# 08_SLAVE_CARD_CONNECTOR_RJ45.net
KiCad netlist of a schematic drawn in Altium Designer
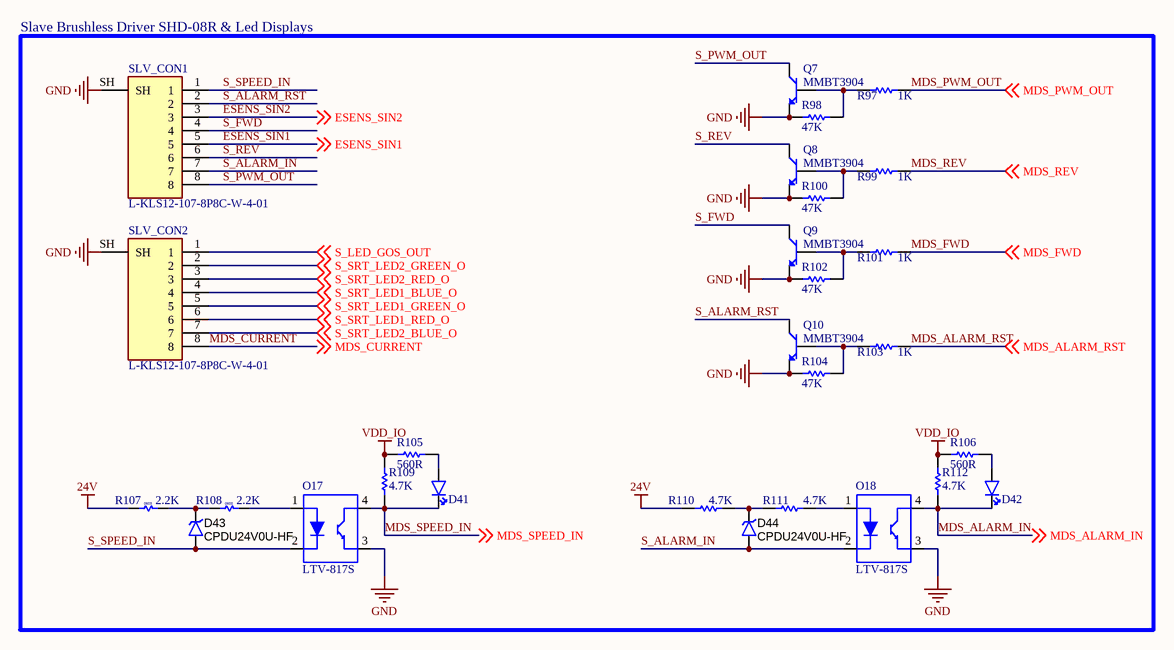
[diagram p0: 08_SLAVE_CARD_CONNECTOR_RJ45.SchDoc]

(export (version "E")
  (design (tool "Eeschema 10.0.6"))
  (components
    (comp (ref "D41")
      (value "led_green")
      (footprint "805LED")
      (description "LED 2X1.2MM 570NM GN WTR CLR SMD")
      (fields (field (name "DIGI-KEY PART NUMBER") "754-1127-1-ND"))
      (libsource (lib "FKDZ_Altium_Lib") (part "LED_GREEN_0805"))
    )
    (comp (ref "D42")
      (value "led_green")
      (footprint "805LED")
      (description "LED 2X1.2MM 570NM GN WTR CLR SMD")
      (fields (field (name "DIGI-KEY PART NUMBER") "754-1127-1-ND"))
      (libsource (lib "FKDZ_Altium_Lib") (part "LED_GREEN_0805"))
    )
    (comp (ref "D43")
      (value "CPDU24V0U-HF")
      (footprint "SOD523F")
      (description "50V Clamp 3A (8/20µs) Ipp Tvs Diode Surface Mount 0603/SOD-523F")
      (fields
        (field (name "DIGI-KEY PART NUMBER") "641-1679-1-ND")
        (field (name "MANUFACTURER") "Comchip Technology")
      )
      (libsource (lib "FKDZ_Altium_Lib") (part "TVS DIODE 24VWM 50V 0603/SOD523F CPDU24V0U-HF"))
    )
    (comp (ref "D44")
      (value "CPDU24V0U-HF")
      (footprint "SOD523F")
      (description "50V Clamp 3A (8/20µs) Ipp Tvs Diode Surface Mount 0603/SOD-523F")
      (fields
        (field (name "DIGI-KEY PART NUMBER") "641-1679-1-ND")
        (field (name "MANUFACTURER") "Comchip Technology")
      )
      (libsource (lib "FKDZ_Altium_Lib") (part "TVS DIODE 24VWM 50V 0603/SOD523F CPDU24V0U-HF"))
    )
    (comp (ref "O17")
      (value "LTV-817S")
      (footprint "SMD4-2.54-4.6X6.5MM")
      (description "Optoisolator Transistor Output 5000Vrms 1 Channel 4-SMD")
      (fields (field (name "DIGI-KEY PART NUMBER") "160-1367-5-ND"))
      (libsource (lib "FKDZ_Altium_Lib") (part "OPTOISOLATR 5KV TRANSISTOR 4-SMD LTV-817S"))
    )
    (comp (ref "O18")
      (value "LTV-817S")
      (footprint "SMD4-2.54-4.6X6.5MM")
      (description "Optoisolator Transistor Output 5000Vrms 1 Channel 4-SMD")
      (fields (field (name "DIGI-KEY PART NUMBER") "160-1367-5-ND"))
      (libsource (lib "FKDZ_Altium_Lib") (part "OPTOISOLATR 5KV TRANSISTOR 4-SMD LTV-817S"))
    )
    (comp (ref "Q7")
      (value "MMBT3904")
      (footprint "ONSC-SOT-23-3-318-08_V")
      (description "Bipolar (BJT) Transistor NPN 40V 200mA 300MHz 300mW Surface Mount SOT-23-3 (TO-236)")
      (fields
        (field (name "DIGI-KEY PART NUMBER") "MMBT3904LT3GOSTR-ND")
        (field (name "MANUFACTURER") "ON Semiconductor")
      )
      (libsource (lib "FKDZ_Altium_Lib") (part "NPN_BT3904"))
    )
    (comp (ref "Q8")
      (value "MMBT3904")
      (footprint "ONSC-SOT-23-3-318-08_V")
      (description "Bipolar (BJT) Transistor NPN 40V 200mA 300MHz 300mW Surface Mount SOT-23-3 (TO-236)")
      (fields
        (field (name "DIGI-KEY PART NUMBER") "MMBT3904LT3GOSTR-ND")
        (field (name "MANUFACTURER") "ON Semiconductor")
      )
      (libsource (lib "FKDZ_Altium_Lib") (part "NPN_BT3904"))
    )
    (comp (ref "Q9")
      (value "MMBT3904")
      (footprint "ONSC-SOT-23-3-318-08_V")
      (description "Bipolar (BJT) Transistor NPN 40V 200mA 300MHz 300mW Surface Mount SOT-23-3 (TO-236)")
      (fields
        (field (name "DIGI-KEY PART NUMBER") "MMBT3904LT3GOSTR-ND")
        (field (name "MANUFACTURER") "ON Semiconductor")
      )
      (libsource (lib "FKDZ_Altium_Lib") (part "NPN_BT3904"))
    )
    (comp (ref "Q10")
      (value "MMBT3904")
      (footprint "ONSC-SOT-23-3-318-08_V")
      (description "Bipolar (BJT) Transistor NPN 40V 200mA 300MHz 300mW Surface Mount SOT-23-3 (TO-236)")
      (fields
        (field (name "DIGI-KEY PART NUMBER") "MMBT3904LT3GOSTR-ND")
        (field (name "MANUFACTURER") "ON Semiconductor")
      )
      (libsource (lib "FKDZ_Altium_Lib") (part "NPN_BT3904"))
    )
    (comp (ref "R97")
      (value "1K")
      (footprint "603R")
      (description "1 kOhms ±5% 0.1W, 1/10W Chip Resistor 0603 (1608 Metric) Moisture Resistant Thick Film")
      (fields (field (name "DIGI-KEY PART NUMBER") "311-1.0KGRTR-ND") (field (name "MANUFACTURER") "Yageo"))
      (libsource (lib "FKDZ_Altium_Lib") (part "RES_1K_OHM_%5_0.1W_0603"))
    )
    (comp (ref "R98")
      (value "47K")
      (footprint "603R")
      (description "47 kOhms ±5% 0.1W, 1/10W Chip Resistor 0603 (1608 Metric) Moisture Resistant Thick Film")
      (fields (field (name "DIGI-KEY PART NUMBER") "311-47KGRTR-ND") (field (name "MANUFACTURER") "Yageo"))
      (libsource (lib "FKDZ_Altium_Lib") (part "RES_47K_OHM_%5_0.1W_0603"))
    )
    (comp (ref "R99")
      (value "1K")
      (footprint "603R")
      (description "1 kOhms ±5% 0.1W, 1/10W Chip Resistor 0603 (1608 Metric) Moisture Resistant Thick Film")
      (fields (field (name "DIGI-KEY PART NUMBER") "311-1.0KGRTR-ND") (field (name "MANUFACTURER") "Yageo"))
      (libsource (lib "FKDZ_Altium_Lib") (part "RES_1K_OHM_%5_0.1W_0603"))
    )
    (comp (ref "R100")
      (value "47K")
      (footprint "603R")
      (description "47 kOhms ±5% 0.1W, 1/10W Chip Resistor 0603 (1608 Metric) Moisture Resistant Thick Film")
      (fields (field (name "DIGI-KEY PART NUMBER") "311-47KGRTR-ND") (field (name "MANUFACTURER") "Yageo"))
      (libsource (lib "FKDZ_Altium_Lib") (part "RES_47K_OHM_%5_0.1W_0603"))
    )
    (comp (ref "R101")
      (value "1K")
      (footprint "603R")
      (description "1 kOhms ±5% 0.1W, 1/10W Chip Resistor 0603 (1608 Metric) Moisture Resistant Thick Film")
      (fields (field (name "DIGI-KEY PART NUMBER") "311-1.0KGRTR-ND") (field (name "MANUFACTURER") "Yageo"))
      (libsource (lib "FKDZ_Altium_Lib") (part "RES_1K_OHM_%5_0.1W_0603"))
    )
    (comp (ref "R102")
      (value "47K")
      (footprint "603R")
      (description "47 kOhms ±5% 0.1W, 1/10W Chip Resistor 0603 (1608 Metric) Moisture Resistant Thick Film")
      (fields (field (name "DIGI-KEY PART NUMBER") "311-47KGRTR-ND") (field (name "MANUFACTURER") "Yageo"))
      (libsource (lib "FKDZ_Altium_Lib") (part "RES_47K_OHM_%5_0.1W_0603"))
    )
    (comp (ref "R103")
      (value "1K")
      (footprint "603R")
      (description "1 kOhms ±5% 0.1W, 1/10W Chip Resistor 0603 (1608 Metric) Moisture Resistant Thick Film")
      (fields (field (name "DIGI-KEY PART NUMBER") "311-1.0KGRTR-ND") (field (name "MANUFACTURER") "Yageo"))
      (libsource (lib "FKDZ_Altium_Lib") (part "RES_1K_OHM_%5_0.1W_0603"))
    )
    (comp (ref "R104")
      (value "47K")
      (footprint "603R")
      (description "47 kOhms ±5% 0.1W, 1/10W Chip Resistor 0603 (1608 Metric) Moisture Resistant Thick Film")
      (fields (field (name "DIGI-KEY PART NUMBER") "311-47KGRTR-ND") (field (name "MANUFACTURER") "Yageo"))
      (libsource (lib "FKDZ_Altium_Lib") (part "RES_47K_OHM_%5_0.1W_0603"))
    )
    (comp (ref "R105")
      (value "560R")
      (footprint "603R")
      (description "560 Ohms ±5% 0.1W, 1/10W Chip Resistor 0603 (1608 Metric) Moisture Resistant Thick Film")
      (fields (field (name "DIGI-KEY PART NUMBER") "311-560GRCT-ND") (field (name "MANUFACTURER") "Yageo"))
      (libsource (lib "FKDZ_Altium_Lib") (part "RES_560_OHM_%5_0.1W_0603"))
    )
    (comp (ref "R106")
      (value "560R")
      (footprint "603R")
      (description "560 Ohms ±5% 0.1W, 1/10W Chip Resistor 0603 (1608 Metric) Moisture Resistant Thick Film")
      (fields (field (name "DIGI-KEY PART NUMBER") "311-560GRCT-ND") (field (name "MANUFACTURER") "Yageo"))
      (libsource (lib "FKDZ_Altium_Lib") (part "RES_560_OHM_%5_0.1W_0603"))
    )
    (comp (ref "R107")
      (value "2.2K")
      (footprint "603R")
      (description "2.2 kOhms ±5% 0.1W, 1/10W Chip Resistor 0603 (1608 Metric) Automotive AEC-Q200 Thick Film")
      (fields (field (name "DIGI-KEY PART NUMBER") "RMCF0603JT2K20TR-ND") (field (name "TOLERANCE") "±5%"))
      (libsource (lib "FKDZ_Altium_Lib") (part "RES 2.2K OHM 5% 1/10W 0603"))
    )
    (comp (ref "R108")
      (value "2.2K")
      (footprint "603R")
      (description "2.2 kOhms ±5% 0.1W, 1/10W Chip Resistor 0603 (1608 Metric) Automotive AEC-Q200 Thick Film")
      (fields (field (name "DIGI-KEY PART NUMBER") "RMCF0603JT2K20TR-ND") (field (name "TOLERANCE") "±5%"))
      (libsource (lib "FKDZ_Altium_Lib") (part "RES 2.2K OHM 5% 1/10W 0603"))
    )
    (comp (ref "R109")
      (value "4.7K")
      (footprint "603R")
      (description "4.7 kOhms ±5% 0.1W, 1/10W Chip Resistor 0603 (1608 Metric) Moisture Resistant Thick Film")
      (fields (field (name "DIGI-KEY PART NUMBER") "311-4.7KGRTR-ND") (field (name "MANUFACTURER") "Yageo"))
      (libsource (lib "FKDZ_Altium_Lib") (part "RES_4.7K_OHM_%5_0.1W_0603"))
    )
    (comp (ref "R110")
      (value "4.7K")
      (footprint "603R")
      (description "4.7 kOhms ±5% 0.1W, 1/10W Chip Resistor 0603 (1608 Metric) Moisture Resistant Thick Film")
      (fields (field (name "DIGI-KEY PART NUMBER") "311-4.7KGRTR-ND") (field (name "MANUFACTURER") "Yageo"))
      (libsource (lib "FKDZ_Altium_Lib") (part "RES_4.7K_OHM_%5_0.1W_0603"))
    )
    (comp (ref "R111")
      (value "4.7K")
      (footprint "603R")
      (description "4.7 kOhms ±5% 0.1W, 1/10W Chip Resistor 0603 (1608 Metric) Moisture Resistant Thick Film")
      (fields (field (name "DIGI-KEY PART NUMBER") "311-4.7KGRTR-ND") (field (name "MANUFACTURER") "Yageo"))
      (libsource (lib "FKDZ_Altium_Lib") (part "RES_4.7K_OHM_%5_0.1W_0603"))
    )
    (comp (ref "R112")
      (value "4.7K")
      (footprint "603R")
      (description "4.7 kOhms ±5% 0.1W, 1/10W Chip Resistor 0603 (1608 Metric) Moisture Resistant Thick Film")
      (fields (field (name "DIGI-KEY PART NUMBER") "311-4.7KGRTR-ND") (field (name "MANUFACTURER") "Yageo"))
      (libsource (lib "FKDZ_Altium_Lib") (part "RES_4.7K_OHM_%5_0.1W_0603"))
    )
    (comp (ref "SLV_CON1")
      (value "L-KLS12-107-8P8C-W-4-01")
      (footprint "RJ45_JACK_H L-KLS12-107-8P8C-W-4-01")
      (description "Jack Modular Connector 8p8c (RJ45, Ethernet) 90° Angle (Right) Shielded")
      (libsource (lib "FKDZ_Altium_Lib") (part "MODULAR JACK THT R/A 8P8C (RJ45,Ethernet) BLACK L-KLS12-107-8P8C-W-4-01"))
    )
    (comp (ref "SLV_CON2")
      (value "L-KLS12-107-8P8C-W-4-01")
      (footprint "RJ45_JACK_H L-KLS12-107-8P8C-W-4-01")
      (description "Jack Modular Connector 8p8c (RJ45, Ethernet) 90° Angle (Right) Shielded")
      (libsource (lib "FKDZ_Altium_Lib") (part "MODULAR JACK THT R/A 8P8C (RJ45,Ethernet) BLACK L-KLS12-107-8P8C-W-4-01"))
    )
  )
  (nets
    (net (code "1") (name "/S_ALARM_IN") (class "Default")
      (node (ref "D44") (pin "1") (pinfunction "1_1") (pintype "passive"))
      (node (ref "O18") (pin "2") (pinfunction "CATHODE_2") (pintype "passive"))
      (node (ref "SLV_CON1") (pin "7") (pinfunction "7_7") (pintype "passive"))
    )
    (net (code "2") (name "/S_ALARM_RST") (class "Default")
      (node (ref "Q10") (pin "3") (pinfunction "C_3") (pintype "passive"))
      (node (ref "SLV_CON1") (pin "2") (pinfunction "2_2") (pintype "passive"))
    )
    (net (code "3") (name "/S_FWD") (class "Default")
      (node (ref "Q9") (pin "3") (pinfunction "C_3") (pintype "passive"))
      (node (ref "SLV_CON1") (pin "4") (pinfunction "4_4") (pintype "passive"))
    )
    (net (code "4") (name "/S_PWM_OUT") (class "Default")
      (node (ref "Q7") (pin "3") (pinfunction "C_3") (pintype "passive"))
      (node (ref "SLV_CON1") (pin "8") (pinfunction "8_8") (pintype "passive"))
    )
    (net (code "5") (name "/S_REV") (class "Default")
      (node (ref "Q8") (pin "3") (pinfunction "C_3") (pintype "passive"))
      (node (ref "SLV_CON1") (pin "6") (pinfunction "6_6") (pintype "passive"))
    )
    (net (code "6") (name "/S_SPEED_IN") (class "Default")
      (node (ref "D43") (pin "1") (pinfunction "1_1") (pintype "passive"))
      (node (ref "O17") (pin "2") (pinfunction "CATHODE_2") (pintype "passive"))
      (node (ref "SLV_CON1") (pin "1") (pinfunction "1_1") (pintype "passive"))
    )
    (net (code "7") (name "24V") (class "Default")
      (node (ref "R107") (pin "1") (pinfunction "1_1") (pintype "passive"))
      (node (ref "R110") (pin "1") (pinfunction "1_1") (pintype "passive"))
    )
    (net (code "8") (name "ESENS_SIN1") (class "Default")
      (node (ref "SLV_CON1") (pin "5") (pinfunction "5_5") (pintype "passive"))
    )
    (net (code "9") (name "ESENS_SIN2") (class "Default")
      (node (ref "SLV_CON1") (pin "3") (pinfunction "3_3") (pintype "passive"))
    )
    (net (code "10") (name "GND") (class "Default")
      (node (ref "O17") (pin "3") (pinfunction "EMITER_3") (pintype "passive"))
      (node (ref "O18") (pin "3") (pinfunction "EMITER_3") (pintype "passive"))
      (node (ref "Q10") (pin "2") (pinfunction "E_2") (pintype "passive"))
      (node (ref "Q7") (pin "2") (pinfunction "E_2") (pintype "passive"))
      (node (ref "Q8") (pin "2") (pinfunction "E_2") (pintype "passive"))
      (node (ref "Q9") (pin "2") (pinfunction "E_2") (pintype "passive"))
      (node (ref "R100") (pin "1") (pinfunction "1_1") (pintype "passive"))
      (node (ref "R102") (pin "1") (pinfunction "1_1") (pintype "passive"))
      (node (ref "R104") (pin "1") (pinfunction "1_1") (pintype "passive"))
      (node (ref "R98") (pin "1") (pinfunction "1_1") (pintype "passive"))
      (node (ref "SLV_CON1") (pin "SH") (pinfunction "SH_SH") (pintype "passive"))
      (node (ref "SLV_CON2") (pin "SH") (pinfunction "SH_SH") (pintype "passive"))
    )
    (net (code "11") (name "MDS_ALARM_IN") (class "Default")
      (node (ref "D42") (pin "2") (pinfunction "K_2") (pintype "passive"))
      (node (ref "O18") (pin "4") (pinfunction "COLLECTOR_4") (pintype "passive"))
      (node (ref "R112") (pin "1") (pinfunction "1_1") (pintype "passive"))
    )
    (net (code "12") (name "MDS_ALARM_RST") (class "Default")
      (node (ref "R103") (pin "2") (pinfunction "2_2") (pintype "passive"))
    )
    (net (code "13") (name "MDS_CURRENT") (class "Default")
      (node (ref "SLV_CON2") (pin "8") (pinfunction "8_8") (pintype "passive"))
    )
    (net (code "14") (name "MDS_FWD") (class "Default")
      (node (ref "R101") (pin "2") (pinfunction "2_2") (pintype "passive"))
    )
    (net (code "15") (name "MDS_PWM_OUT") (class "Default")
      (node (ref "R97") (pin "2") (pinfunction "2_2") (pintype "passive"))
    )
    (net (code "16") (name "MDS_REV") (class "Default")
      (node (ref "R99") (pin "2") (pinfunction "2_2") (pintype "passive"))
    )
    (net (code "17") (name "MDS_SPEED_IN") (class "Default")
      (node (ref "D41") (pin "2") (pinfunction "K_2") (pintype "passive"))
      (node (ref "O17") (pin "4") (pinfunction "COLLECTOR_4") (pintype "passive"))
      (node (ref "R109") (pin "1") (pinfunction "1_1") (pintype "passive"))
    )
    (net (code "18") (name "Net-(D41-A)") (class "Default")
      (node (ref "D41") (pin "1") (pinfunction "A_1") (pintype "passive"))
      (node (ref "R105") (pin "1") (pinfunction "1_1") (pintype "passive"))
    )
    (net (code "19") (name "Net-(D42-A)") (class "Default")
      (node (ref "D42") (pin "1") (pinfunction "A_1") (pintype "passive"))
      (node (ref "R106") (pin "1") (pinfunction "1_1") (pintype "passive"))
    )
    (net (code "20") (name "Net-(D43-Pad2)") (class "Default")
      (node (ref "D43") (pin "2") (pinfunction "2_2") (pintype "passive"))
      (node (ref "R107") (pin "2") (pinfunction "2_2") (pintype "passive"))
      (node (ref "R108") (pin "1") (pinfunction "1_1") (pintype "passive"))
    )
    (net (code "21") (name "Net-(D44-Pad2)") (class "Default")
      (node (ref "D44") (pin "2") (pinfunction "2_2") (pintype "passive"))
      (node (ref "R110") (pin "2") (pinfunction "2_2") (pintype "passive"))
      (node (ref "R111") (pin "1") (pinfunction "1_1") (pintype "passive"))
    )
    (net (code "22") (name "Net-(O17-ANODE)") (class "Default")
      (node (ref "O17") (pin "1") (pinfunction "ANODE_1") (pintype "passive"))
      (node (ref "R108") (pin "2") (pinfunction "2_2") (pintype "passive"))
    )
    (net (code "23") (name "Net-(O18-ANODE)") (class "Default")
      (node (ref "O18") (pin "1") (pinfunction "ANODE_1") (pintype "passive"))
      (node (ref "R111") (pin "2") (pinfunction "2_2") (pintype "passive"))
    )
    (net (code "24") (name "Net-(Q7-B)") (class "Default")
      (node (ref "Q7") (pin "1") (pinfunction "B_1") (pintype "passive"))
      (node (ref "R97") (pin "1") (pinfunction "1_1") (pintype "passive"))
      (node (ref "R98") (pin "2") (pinfunction "2_2") (pintype "passive"))
    )
    (net (code "25") (name "Net-(Q8-B)") (class "Default")
      (node (ref "Q8") (pin "1") (pinfunction "B_1") (pintype "passive"))
      (node (ref "R100") (pin "2") (pinfunction "2_2") (pintype "passive"))
      (node (ref "R99") (pin "1") (pinfunction "1_1") (pintype "passive"))
    )
    (net (code "26") (name "Net-(Q9-B)") (class "Default")
      (node (ref "Q9") (pin "1") (pinfunction "B_1") (pintype "passive"))
      (node (ref "R101") (pin "1") (pinfunction "1_1") (pintype "passive"))
      (node (ref "R102") (pin "2") (pinfunction "2_2") (pintype "passive"))
    )
    (net (code "27") (name "Net-(Q10-B)") (class "Default")
      (node (ref "Q10") (pin "1") (pinfunction "B_1") (pintype "passive"))
      (node (ref "R103") (pin "1") (pinfunction "1_1") (pintype "passive"))
      (node (ref "R104") (pin "2") (pinfunction "2_2") (pintype "passive"))
    )
    (net (code "28") (name "S_LED_GOS_OUT") (class "Default")
      (node (ref "SLV_CON2") (pin "1") (pinfunction "1_1") (pintype "passive"))
    )
    (net (code "29") (name "S_SRT_LED1_BLUE_O") (class "Default")
      (node (ref "SLV_CON2") (pin "4") (pinfunction "4_4") (pintype "passive"))
    )
    (net (code "30") (name "S_SRT_LED1_GREEN_O") (class "Default")
      (node (ref "SLV_CON2") (pin "5") (pinfunction "5_5") (pintype "passive"))
    )
    (net (code "31") (name "S_SRT_LED1_RED_O") (class "Default")
      (node (ref "SLV_CON2") (pin "6") (pinfunction "6_6") (pintype "passive"))
    )
    (net (code "32") (name "S_SRT_LED2_BLUE_O") (class "Default")
      (node (ref "SLV_CON2") (pin "7") (pinfunction "7_7") (pintype "passive"))
    )
    (net (code "33") (name "S_SRT_LED2_GREEN_O") (class "Default")
      (node (ref "SLV_CON2") (pin "2") (pinfunction "2_2") (pintype "passive"))
    )
    (net (code "34") (name "S_SRT_LED2_RED_O") (class "Default")
      (node (ref "SLV_CON2") (pin "3") (pinfunction "3_3") (pintype "passive"))
    )
    (net (code "35") (name "VDD_IO") (class "Default")
      (node (ref "R105") (pin "2") (pinfunction "2_2") (pintype "passive"))
      (node (ref "R106") (pin "2") (pinfunction "2_2") (pintype "passive"))
      (node (ref "R109") (pin "2") (pinfunction "2_2") (pintype "passive"))
      (node (ref "R112") (pin "2") (pinfunction "2_2") (pintype "passive"))
    )
  )
)
